# Dynamug_PCB_Final_Draft.net
KiCad netlist of a schematic drawn in EAGLE
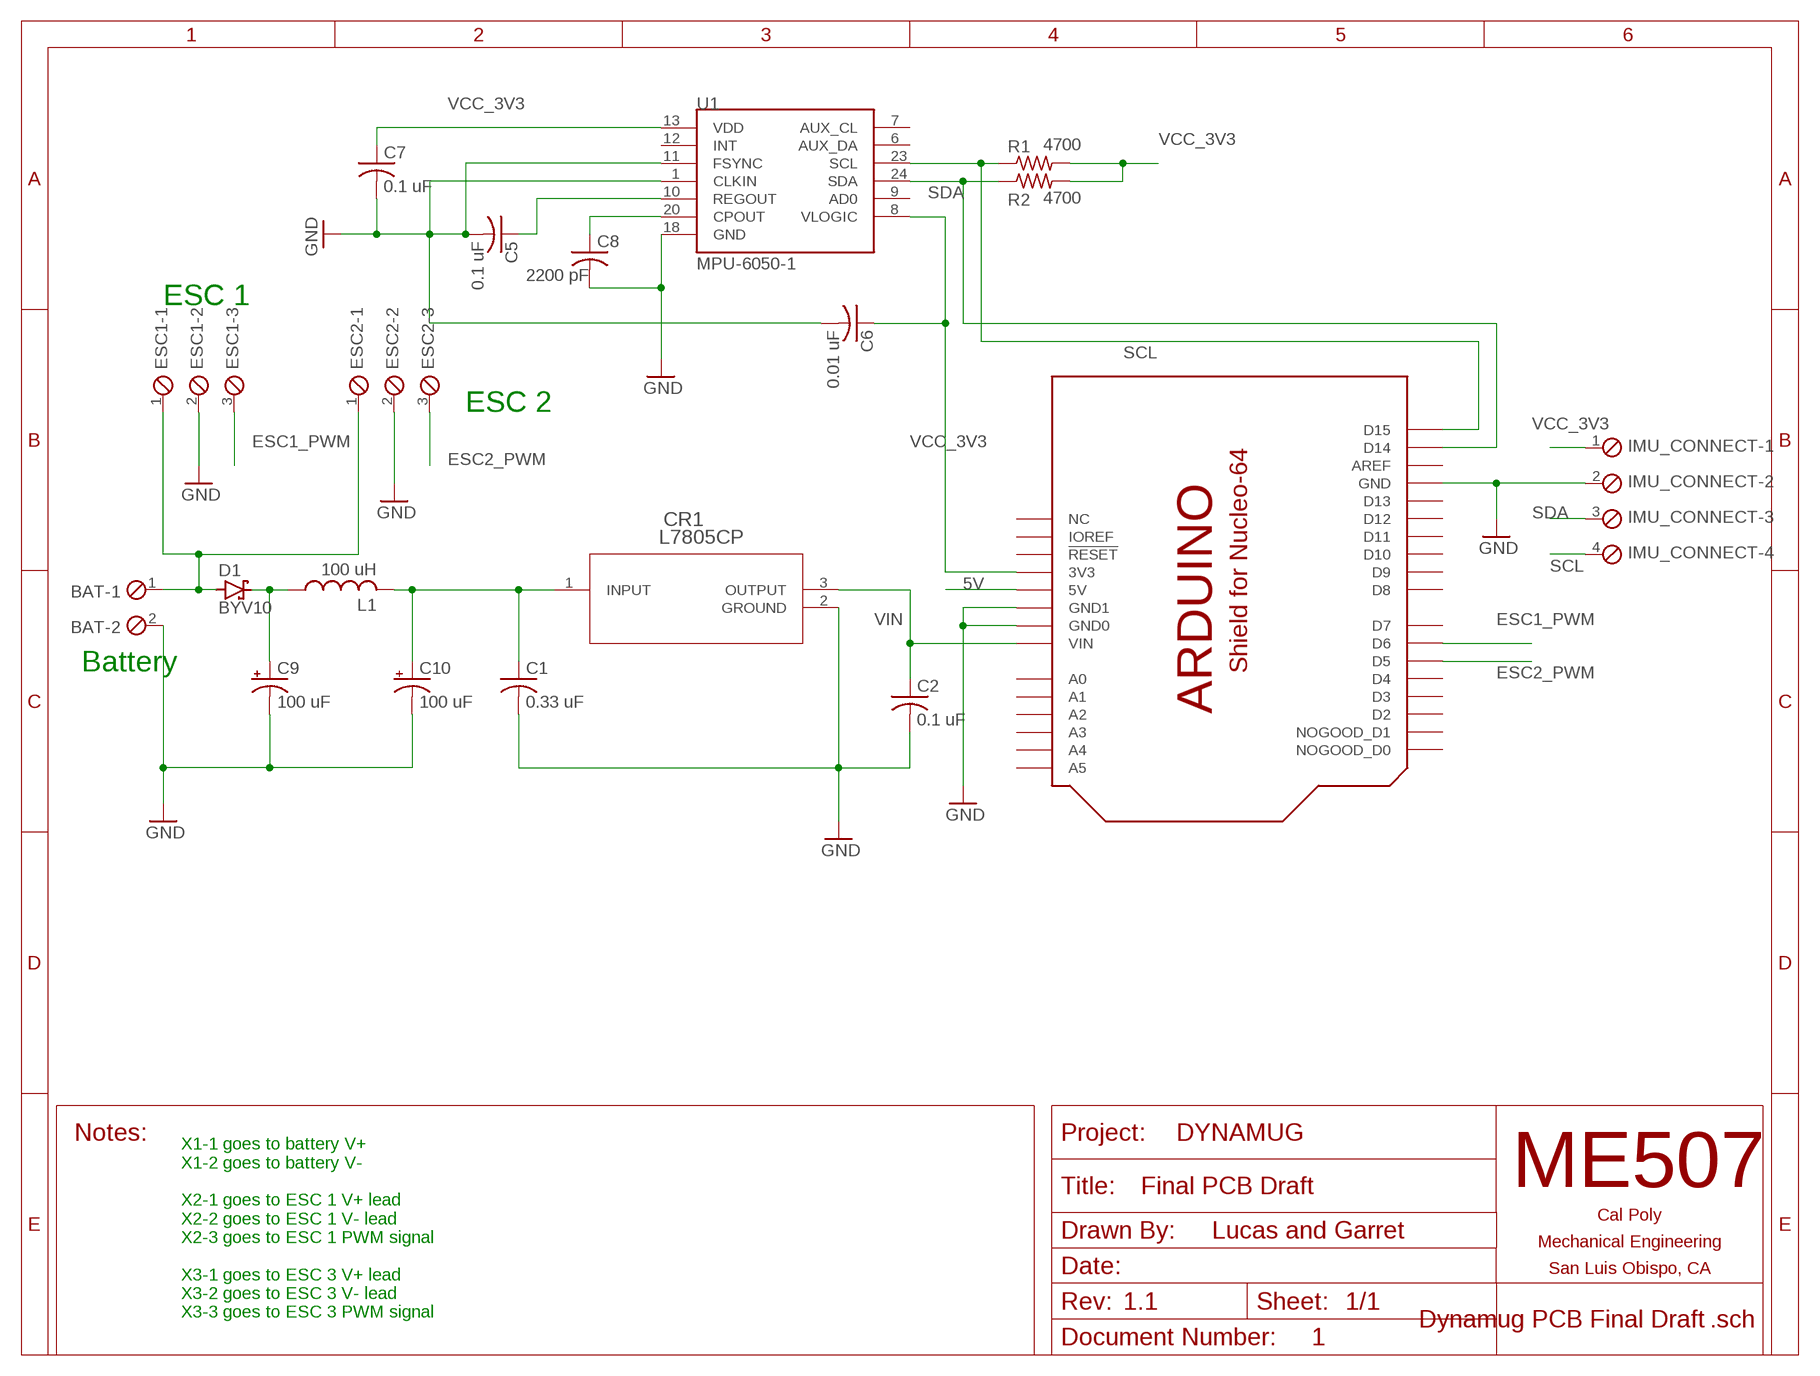
[diagram p0: schematic, sheet 1]

(export (version "E")
  (design (tool "Eeschema 10.0.6"))
  (components
    (comp (ref "BAT")
      (value "SCREWTERM_2P_381")
      (footprint "eagle-import:2POL381")
      (libsource (lib "eagle-import") (part "SCREWTERM_2P_381"))
    )
    (comp (ref "C1")
      (value "0.33 uF")
      (footprint "eagle-import:C0805")
      (libsource (lib "eagle-import") (part "C-USC0805"))
    )
    (comp (ref "C2")
      (value "0.1 uF")
      (footprint "eagle-import:C0805")
      (libsource (lib "eagle-import") (part "C-USC0805"))
    )
    (comp (ref "C5")
      (value "0.1 uF")
      (footprint "eagle-import:C0805")
      (libsource (lib "eagle-import") (part "C-USC0805"))
    )
    (comp (ref "C6")
      (value "0.01 uF")
      (footprint "eagle-import:C0805")
      (libsource (lib "eagle-import") (part "C-USC0805"))
    )
    (comp (ref "C7")
      (value "0.1 uF")
      (footprint "eagle-import:C0805")
      (libsource (lib "eagle-import") (part "C-USC0805"))
    )
    (comp (ref "C8")
      (value "2200 pF")
      (footprint "eagle-import:C0805")
      (libsource (lib "eagle-import") (part "C-USC0805"))
    )
    (comp (ref "C9")
      (value "100 uF")
      (footprint "eagle-import:E2,5-6")
      (libsource (lib "eagle-import") (part "CPOL-USE2.5-6"))
    )
    (comp (ref "C10")
      (value "100 uF")
      (footprint "eagle-import:E2,5-6")
      (libsource (lib "eagle-import") (part "CPOL-USE2.5-6"))
    )
    (comp (ref "CR1")
      (value "L7805CP")
      (footprint "eagle-import:TO-220FP_STM")
      (fields (field (name "COPYRIGHT") "Copyright (C) 2021 Ultra Librarian. All rights reserved."))
      (libsource (lib "eagle-import") (part "L7805CP"))
    )
    (comp (ref "D1")
      (value "BYV10")
      (footprint "eagle-import:DO41-10")
      (libsource (lib "eagle-import") (part "BYV10"))
    )
    (comp (ref "ESC1")
      (value "SCREWTERM_3P_381")
      (footprint "eagle-import:3POL381")
      (libsource (lib "eagle-import") (part "SCREWTERM_3P_381"))
    )
    (comp (ref "ESC2")
      (value "SCREWTERM_3P_381")
      (footprint "eagle-import:3POL381")
      (libsource (lib "eagle-import") (part "SCREWTERM_3P_381"))
    )
    (comp (ref "IMU_CONNECT")
      (value "SCREWTERM_4P_381")
      (footprint "eagle-import:4POL381")
      (libsource (lib "eagle-import") (part "SCREWTERM_4P_381"))
    )
    (comp (ref "L1")
      (value "100 uH")
      (footprint "eagle-import:LAL03")
      (libsource (lib "eagle-import") (part "L-USLAL03"))
    )
    (comp (ref "R1")
      (value "4700")
      (footprint "eagle-import:R2010")
      (libsource (lib "eagle-import") (part "R-US_R2010"))
    )
    (comp (ref "R2")
      (value "4700")
      (footprint "eagle-import:R2010")
      (libsource (lib "eagle-import") (part "R-US_R2010"))
    )
    (comp (ref "U$1")
      (value "SHIELD_FOR_NUCLE0_64_SHORT")
      (footprint "eagle-import:SHIELD_FOR_NUCLEO_64_SHORT")
      (libsource (lib "eagle-import") (part "SHIELD_FOR_NUCLE0_64_SHORT"))
    )
    (comp (ref "U1")
      (value "MPU-6050-1")
      (footprint "eagle-import:QFN-24-4MM2")
      (libsource (lib "eagle-import") (part "MPU-6050-1"))
    )
  )
  (nets
    (net (code "1") (name "/5V") (class "Default")
      (node (ref "U$1") (pin "5V") (pinfunction "5V_5V") (pintype "power_in"))
    )
    (net (code "2") (name "/ESC1_PWM") (class "Default")
      (node (ref "ESC1") (pin "3") (pinfunction "1_3") (pintype "passive"))
      (node (ref "U$1") (pin "D6") (pinfunction "D6_D6") (pintype "bidirectional"))
    )
    (net (code "3") (name "/ESC2_PWM") (class "Default")
      (node (ref "ESC2") (pin "3") (pinfunction "1_3") (pintype "passive"))
      (node (ref "U$1") (pin "D5") (pinfunction "D5_D5") (pintype "bidirectional"))
    )
    (net (code "4") (name "/SCL") (class "Default")
      (node (ref "IMU_CONNECT") (pin "4") (pinfunction "1_4") (pintype "passive"))
      (node (ref "R1") (pin "1") (pinfunction "1_1") (pintype "passive"))
      (node (ref "U$1") (pin "D15") (pinfunction "D15_D15") (pintype "bidirectional"))
      (node (ref "U1") (pin "23") (pinfunction "SCL_23") (pintype "bidirectional"))
    )
    (net (code "5") (name "/SDA") (class "Default")
      (node (ref "IMU_CONNECT") (pin "3") (pinfunction "1_3") (pintype "passive"))
      (node (ref "R2") (pin "1") (pinfunction "1_1") (pintype "passive"))
      (node (ref "U$1") (pin "D14") (pinfunction "D14_D14") (pintype "bidirectional"))
      (node (ref "U1") (pin "24") (pinfunction "SDA_24") (pintype "bidirectional"))
    )
    (net (code "6") (name "/VCC_3V3") (class "Default")
      (node (ref "C6") (pin "1") (pinfunction "1_1") (pintype "passive"))
      (node (ref "C7") (pin "1") (pinfunction "1_1") (pintype "passive"))
      (node (ref "IMU_CONNECT") (pin "1") (pinfunction "1_1") (pintype "passive"))
      (node (ref "R1") (pin "2") (pinfunction "2_2") (pintype "passive"))
      (node (ref "R2") (pin "2") (pinfunction "2_2") (pintype "passive"))
      (node (ref "U$1") (pin "3V") (pinfunction "3V3_3V") (pintype "power_in"))
      (node (ref "U1") (pin "13") (pinfunction "VDD_13") (pintype "bidirectional"))
      (node (ref "U1") (pin "8") (pinfunction "VLOGIC_8") (pintype "bidirectional"))
    )
    (net (code "7") (name "/VIN") (class "Default")
      (node (ref "C2") (pin "1") (pinfunction "1_1") (pintype "passive"))
      (node (ref "CR1") (pin "3") (pinfunction "OUTPUT_3") (pintype "output"))
      (node (ref "U$1") (pin "VIN") (pinfunction "VIN_VIN") (pintype "power_in"))
    )
    (net (code "8") (name "GND") (class "Default")
      (node (ref "BAT") (pin "2") (pinfunction "1_2") (pintype "passive"))
      (node (ref "C1") (pin "2") (pinfunction "2_2") (pintype "passive"))
      (node (ref "C10") (pin "-") (pinfunction "-_-") (pintype "passive"))
      (node (ref "C2") (pin "2") (pinfunction "2_2") (pintype "passive"))
      (node (ref "C5") (pin "2") (pinfunction "2_2") (pintype "passive"))
      (node (ref "C6") (pin "2") (pinfunction "2_2") (pintype "passive"))
      (node (ref "C7") (pin "2") (pinfunction "2_2") (pintype "passive"))
      (node (ref "C8") (pin "2") (pinfunction "2_2") (pintype "passive"))
      (node (ref "C9") (pin "-") (pinfunction "-_-") (pintype "passive"))
      (node (ref "CR1") (pin "2") (pinfunction "GROUND_2") (pintype "power_in"))
      (node (ref "ESC1") (pin "2") (pinfunction "1_2") (pintype "passive"))
      (node (ref "ESC2") (pin "2") (pinfunction "1_2") (pintype "passive"))
      (node (ref "IMU_CONNECT") (pin "2") (pinfunction "1_2") (pintype "passive"))
      (node (ref "U$1") (pin "GND") (pinfunction "GND_GND") (pintype "power_in"))
      (node (ref "U$1") (pin "GND1") (pinfunction "GND0_GND1") (pintype "power_in"))
      (node (ref "U$1") (pin "GND2") (pinfunction "GND1_GND2") (pintype "power_in"))
      (node (ref "U1") (pin "1") (pinfunction "CLKIN_1") (pintype "bidirectional"))
      (node (ref "U1") (pin "11") (pinfunction "FSYNC_11") (pintype "bidirectional"))
      (node (ref "U1") (pin "18") (pinfunction "GND_18") (pintype "bidirectional"))
    )
    (net (code "9") (name "Net-(BAT-Pad1)") (class "Default")
      (node (ref "BAT") (pin "1") (pinfunction "1_1") (pintype "passive"))
      (node (ref "D1") (pin "A") (pinfunction "A_A") (pintype "passive"))
      (node (ref "ESC1") (pin "1") (pinfunction "1_1") (pintype "passive"))
      (node (ref "ESC2") (pin "1") (pinfunction "1_1") (pintype "passive"))
    )
    (net (code "10") (name "Net-(C9-Pad+)") (class "Default")
      (node (ref "C9") (pin "+") (pinfunction "+_+") (pintype "passive"))
      (node (ref "D1") (pin "C") (pinfunction "C_C") (pintype "passive"))
      (node (ref "L1") (pin "1") (pinfunction "1_1") (pintype "passive"))
    )
    (net (code "11") (name "Net-(CR1-INPUT)") (class "Default")
      (node (ref "C1") (pin "1") (pinfunction "1_1") (pintype "passive"))
      (node (ref "C10") (pin "+") (pinfunction "+_+") (pintype "passive"))
      (node (ref "CR1") (pin "1") (pinfunction "INPUT_1") (pintype "input"))
      (node (ref "L1") (pin "2") (pinfunction "2_2") (pintype "passive"))
    )
    (net (code "12") (name "Net-(U1-CPOUT)") (class "Default")
      (node (ref "C8") (pin "1") (pinfunction "1_1") (pintype "passive"))
      (node (ref "U1") (pin "20") (pinfunction "CPOUT_20") (pintype "bidirectional"))
    )
    (net (code "13") (name "Net-(U1-REGOUT)") (class "Default")
      (node (ref "C5") (pin "1") (pinfunction "1_1") (pintype "passive"))
      (node (ref "U1") (pin "10") (pinfunction "REGOUT_10") (pintype "bidirectional"))
    )
    (net (code "14") (name "unconnected-(U$1-NOGOOD_D0-PadD0)") (class "Default")
      (node (ref "U$1") (pin "D0") (pinfunction "NOGOOD_D0_D0") (pintype "no_connect"))
    )
    (net (code "15") (name "unconnected-(U$1-NOGOOD_D1-PadD1)") (class "Default")
      (node (ref "U$1") (pin "D1") (pinfunction "NOGOOD_D1_D1") (pintype "no_connect"))
    )
    (net (code "16") (name "unconnected-(U$1-PadA0)") (class "Default")
      (node (ref "U$1") (pin "A0") (pinfunction "A0_A0") (pintype "bidirectional"))
    )
    (net (code "17") (name "unconnected-(U$1-PadA1)") (class "Default")
      (node (ref "U$1") (pin "A1") (pinfunction "A1_A1") (pintype "bidirectional"))
    )
    (net (code "18") (name "unconnected-(U$1-PadA2)") (class "Default")
      (node (ref "U$1") (pin "A2") (pinfunction "A2_A2") (pintype "bidirectional"))
    )
    (net (code "19") (name "unconnected-(U$1-PadA3)") (class "Default")
      (node (ref "U$1") (pin "A3") (pinfunction "A3_A3") (pintype "bidirectional"))
    )
    (net (code "20") (name "unconnected-(U$1-PadA4)") (class "Default")
      (node (ref "U$1") (pin "A4") (pinfunction "A4_A4") (pintype "bidirectional"))
    )
    (net (code "21") (name "unconnected-(U$1-PadA5)") (class "Default")
      (node (ref "U$1") (pin "A5") (pinfunction "A5_A5") (pintype "bidirectional"))
    )
    (net (code "22") (name "unconnected-(U$1-PadAREF)") (class "Default")
      (node (ref "U$1") (pin "AREF") (pinfunction "AREF_AREF") (pintype "bidirectional"))
    )
    (net (code "23") (name "unconnected-(U$1-PadD2)") (class "Default")
      (node (ref "U$1") (pin "D2") (pinfunction "D2_D2") (pintype "bidirectional"))
    )
    (net (code "24") (name "unconnected-(U$1-PadD3)") (class "Default")
      (node (ref "U$1") (pin "D3") (pinfunction "D3_D3") (pintype "bidirectional"))
    )
    (net (code "25") (name "unconnected-(U$1-PadD4)") (class "Default")
      (node (ref "U$1") (pin "D4") (pinfunction "D4_D4") (pintype "bidirectional"))
    )
    (net (code "26") (name "unconnected-(U$1-PadD7)") (class "Default")
      (node (ref "U$1") (pin "D7") (pinfunction "D7_D7") (pintype "bidirectional"))
    )
    (net (code "27") (name "unconnected-(U$1-PadD8)") (class "Default")
      (node (ref "U$1") (pin "D8") (pinfunction "D8_D8") (pintype "bidirectional"))
    )
    (net (code "28") (name "unconnected-(U$1-PadD9)") (class "Default")
      (node (ref "U$1") (pin "D9") (pinfunction "D9_D9") (pintype "bidirectional"))
    )
    (net (code "29") (name "unconnected-(U$1-PadD10)") (class "Default")
      (node (ref "U$1") (pin "D10") (pinfunction "D10_D10") (pintype "bidirectional"))
    )
    (net (code "30") (name "unconnected-(U$1-PadD11)") (class "Default")
      (node (ref "U$1") (pin "D11") (pinfunction "D11_D11") (pintype "bidirectional"))
    )
    (net (code "31") (name "unconnected-(U$1-PadD12)") (class "Default")
      (node (ref "U$1") (pin "D12") (pinfunction "D12_D12") (pintype "bidirectional"))
    )
    (net (code "32") (name "unconnected-(U$1-PadD13)") (class "Default")
      (node (ref "U$1") (pin "D13") (pinfunction "D13_D13") (pintype "bidirectional"))
    )
    (net (code "33") (name "unconnected-(U$1-PadIOREF)") (class "Default")
      (node (ref "U$1") (pin "IOREF") (pinfunction "IOREF_IOREF") (pintype "bidirectional"))
    )
    (net (code "34") (name "unconnected-(U$1-PadNC)") (class "Default")
      (node (ref "U$1") (pin "NC") (pinfunction "NC_NC") (pintype "no_connect"))
    )
    (net (code "35") (name "unconnected-(U$1-~{RESET}-PadNRST)") (class "Default")
      (node (ref "U$1") (pin "NRST") (pinfunction "~{RESET}_NRST") (pintype "input"))
    )
    (net (code "36") (name "unconnected-(U1-AD0-Pad9)") (class "Default")
      (node (ref "U1") (pin "9") (pinfunction "AD0_9") (pintype "bidirectional"))
    )
    (net (code "37") (name "unconnected-(U1-AUX_CL-Pad7)") (class "Default")
      (node (ref "U1") (pin "7") (pinfunction "AUX_CL_7") (pintype "bidirectional"))
    )
    (net (code "38") (name "unconnected-(U1-AUX_DA-Pad6)") (class "Default")
      (node (ref "U1") (pin "6") (pinfunction "AUX_DA_6") (pintype "bidirectional"))
    )
    (net (code "39") (name "unconnected-(U1-INT-Pad12)") (class "Default")
      (node (ref "U1") (pin "12") (pinfunction "INT_12") (pintype "bidirectional"))
    )
  )
)
